# DisplayPort.net
KiCad netlist of a schematic drawn in Altium Designer
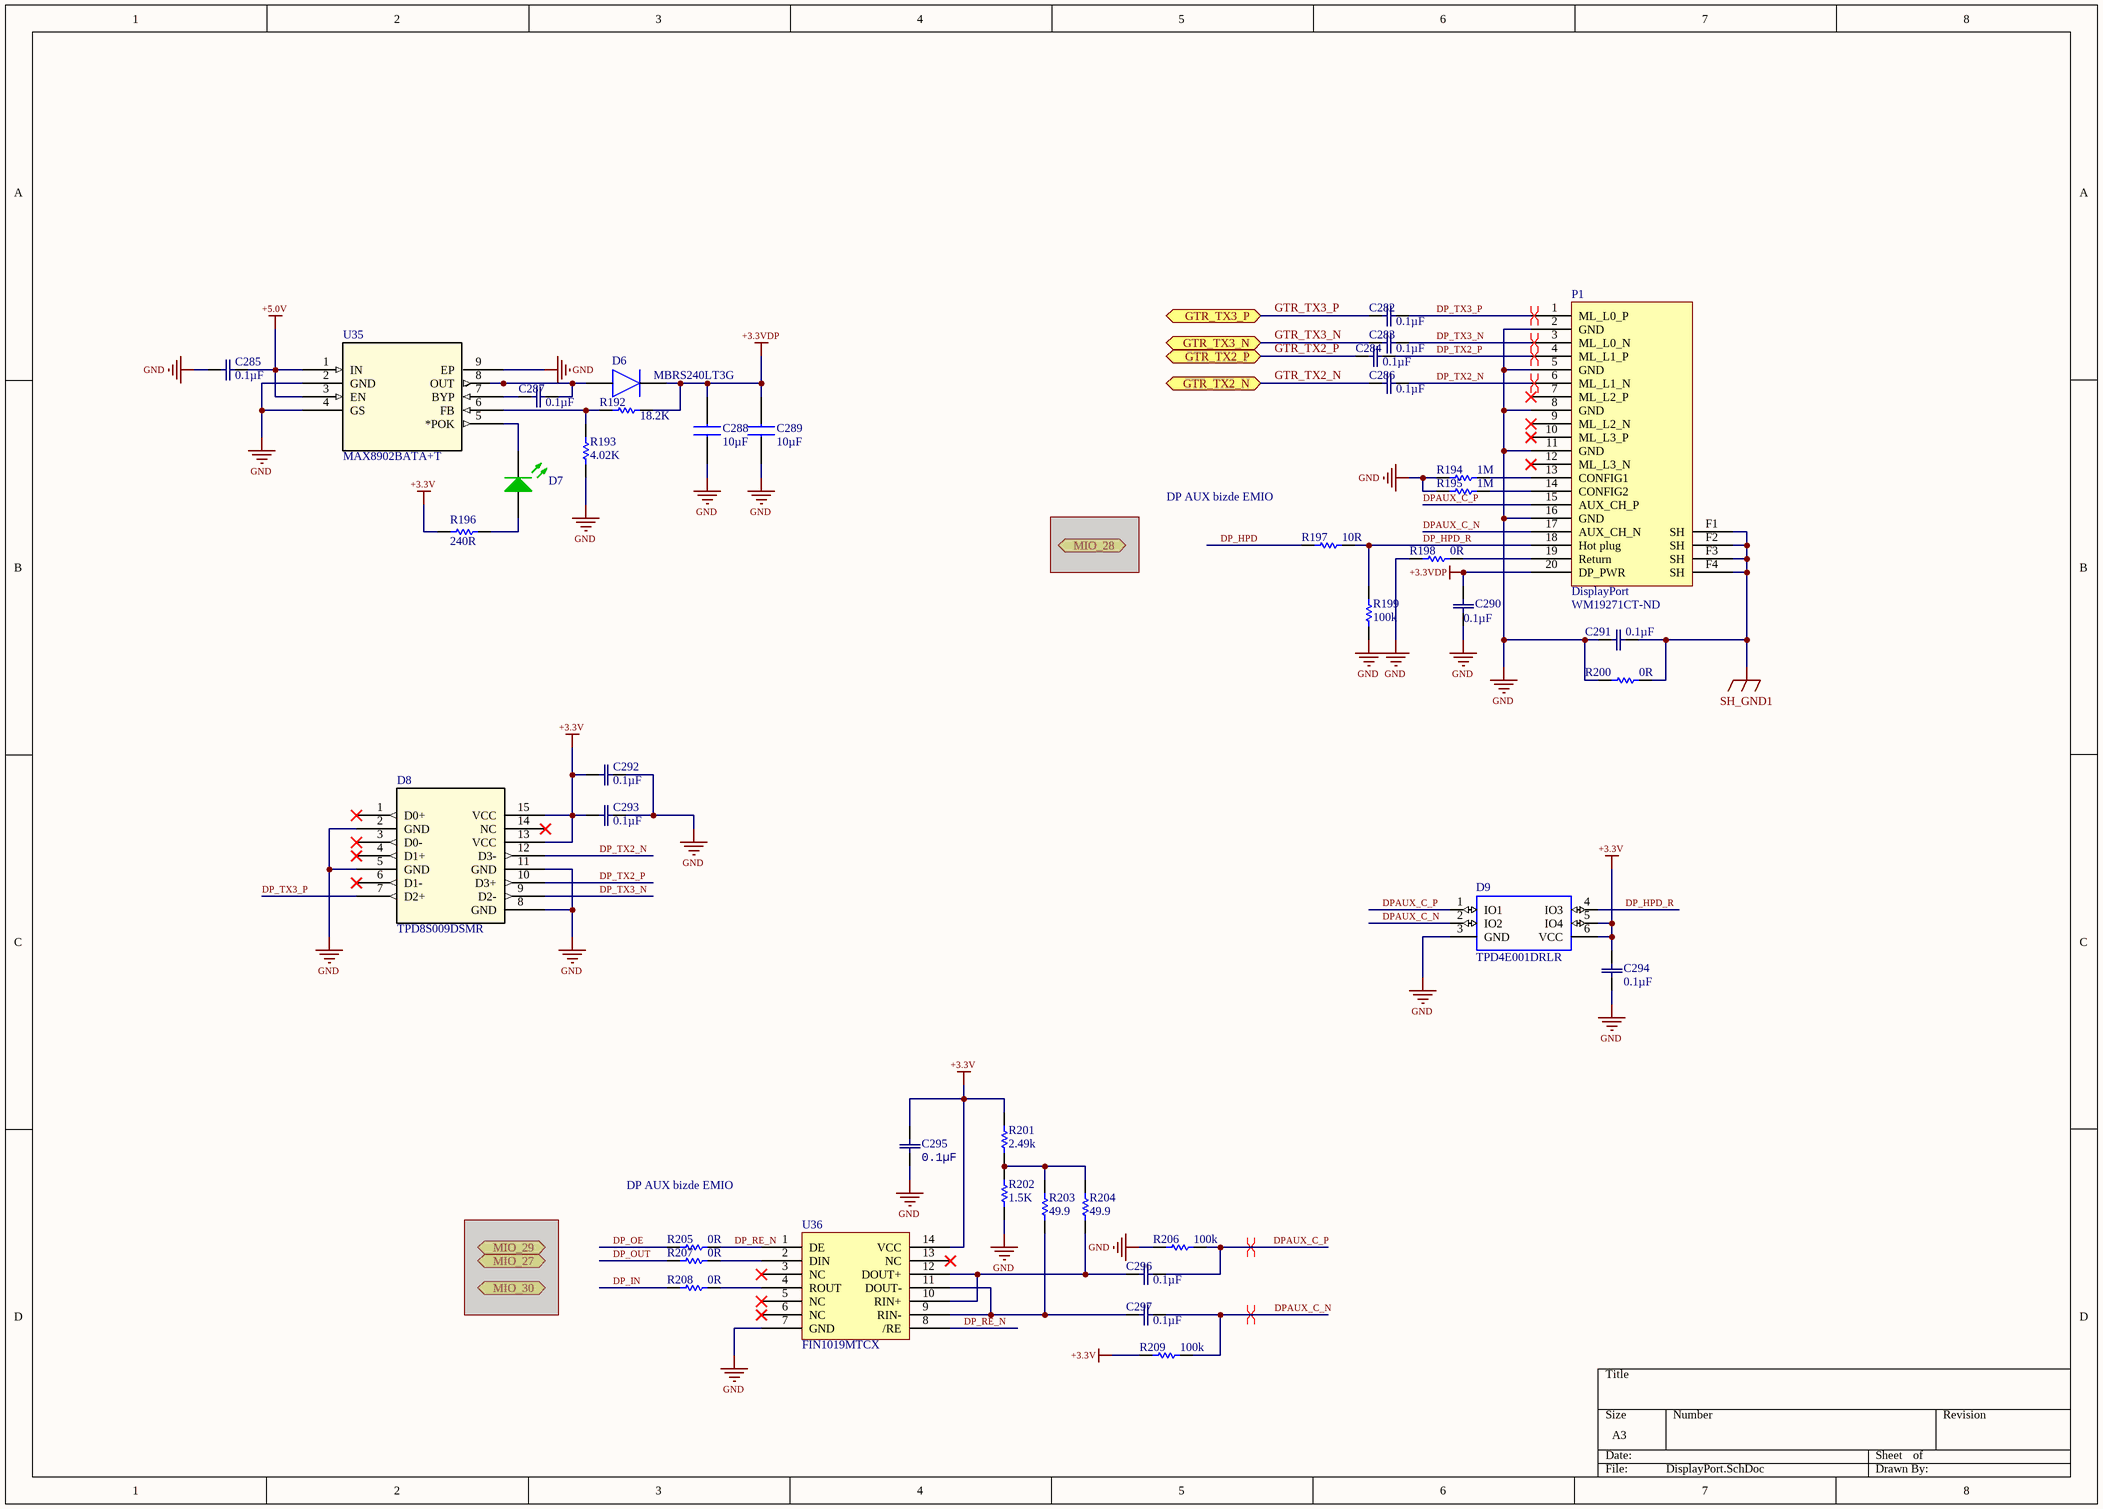
[diagram p0: DisplayPort.SchDoc]

(export (version "E")
  (design (tool "Eeschema 10.0.6"))
  (components
    (comp (ref "C282")
      (value "0.1µF")
      (footprint "CAP_0603")
      (description "CAP CER 0.1UF 25V 10% X5R 0201")
      (fields
        (field (name "MANUFACTURER_PART_NUMBER") "C0603X5R1E104K030BB")
        (field (name "DIGI-KEY PART NUMBER") "445-13671-1-ND")
      )
      (libsource (lib "Ultrascale_SchLib") (part "C0603X5R1E104K030BB"))
    )
    (comp (ref "C283")
      (value "0.1µF")
      (footprint "CAP_0603")
      (description "CAP CER 0.1UF 25V 10% X5R 0201")
      (fields
        (field (name "MANUFACTURER_PART_NUMBER") "C0603X5R1E104K030BB")
        (field (name "DIGI-KEY PART NUMBER") "445-13671-1-ND")
      )
      (libsource (lib "Ultrascale_SchLib") (part "C0603X5R1E104K030BB"))
    )
    (comp (ref "C284")
      (value "0.1µF")
      (footprint "CAP_0603")
      (description "CAP CER 0.1UF 25V 10% X5R 0201")
      (fields
        (field (name "MANUFACTURER_PART_NUMBER") "C0603X5R1E104K030BB")
        (field (name "DIGI-KEY PART NUMBER") "445-13671-1-ND")
      )
      (libsource (lib "Ultrascale_SchLib") (part "C0603X5R1E104K030BB"))
    )
    (comp (ref "C285")
      (value "0.1µF")
      (footprint "CAP_0603")
      (description "CAP CER 0.1UF 25V 10% X5R 0201")
      (fields
        (field (name "MANUFACTURER_PART_NUMBER") "C0603X5R1E104K030BB")
        (field (name "DIGI-KEY PART NUMBER") "445-13671-1-ND")
      )
      (libsource (lib "Ultrascale_SchLib") (part "C0603X5R1E104K030BB"))
    )
    (comp (ref "C286")
      (value "0.1µF")
      (footprint "CAP_0603")
      (description "CAP CER 0.1UF 25V 10% X5R 0201")
      (fields
        (field (name "MANUFACTURER_PART_NUMBER") "C0603X5R1E104K030BB")
        (field (name "DIGI-KEY PART NUMBER") "445-13671-1-ND")
      )
      (libsource (lib "Ultrascale_SchLib") (part "C0603X5R1E104K030BB"))
    )
    (comp (ref "C287")
      (value "0.1µF")
      (footprint "CAP_0603")
      (description "CAP CER 0.1UF 25V 10% X5R 0201")
      (fields
        (field (name "MANUFACTURER_PART_NUMBER") "C0603X5R1E104K030BB")
        (field (name "DIGI-KEY PART NUMBER") "445-13671-1-ND")
      )
      (libsource (lib "Ultrascale_SchLib") (part "C0603X5R1E104K030BB"))
    )
    (comp (ref "C288")
      (value "10µF")
      (footprint "CAP 0402ZD106")
      (description "CAP CER 10UF 10V X5R 0402")
      (fields
        (field (name "MANUFACTURER_PART_NUMBER") "0402ZD106MAT2A")
        (field (name "DIGI-KEY PART NUMBER") "478-10052-1-ND")
      )
      (libsource (lib "Ultrascale_SchLib") (part "CAP 0402ZD106"))
    )
    (comp (ref "C289")
      (value "10µF")
      (footprint "CAP 0402ZD106")
      (description "CAP CER 10UF 10V X5R 0402")
      (fields
        (field (name "MANUFACTURER_PART_NUMBER") "0402ZD106MAT2A")
        (field (name "DIGI-KEY PART NUMBER") "478-10052-1-ND")
      )
      (libsource (lib "Ultrascale_SchLib") (part "CAP 0402ZD106"))
    )
    (comp (ref "C290")
      (value "0.1µF")
      (footprint "CAP_0603")
      (description "CAP CER 0.1UF 25V 10% X5R 0201")
      (fields
        (field (name "MANUFACTURER_PART_NUMBER") "C0603X5R1E104K030BB")
        (field (name "DIGI-KEY PART NUMBER") "445-13671-1-ND")
      )
      (libsource (lib "Ultrascale_SchLib") (part "C0603X5R1E104K030BB"))
    )
    (comp (ref "C291")
      (value "0.1µF")
      (footprint "CAP_0603")
      (description "CAP CER 0.1UF 25V 10% X5R 0201")
      (fields
        (field (name "MANUFACTURER_PART_NUMBER") "C0603X5R1E104K030BB")
        (field (name "DIGI-KEY PART NUMBER") "445-13671-1-ND")
      )
      (libsource (lib "Ultrascale_SchLib") (part "C0603X5R1E104K030BB"))
    )
    (comp (ref "C292")
      (value "0.1µF")
      (footprint "CAP_0603")
      (description "CAP CER 0.1UF 25V 10% X5R 0201")
      (fields
        (field (name "MANUFACTURER_PART_NUMBER") "C0603X5R1E104K030BB")
        (field (name "DIGI-KEY PART NUMBER") "445-13671-1-ND")
      )
      (libsource (lib "Ultrascale_SchLib") (part "C0603X5R1E104K030BB"))
    )
    (comp (ref "C293")
      (value "0.1µF")
      (footprint "CAP_0603")
      (description "CAP CER 0.1UF 25V 10% X5R 0201")
      (fields
        (field (name "MANUFACTURER_PART_NUMBER") "C0603X5R1E104K030BB")
        (field (name "DIGI-KEY PART NUMBER") "445-13671-1-ND")
      )
      (libsource (lib "Ultrascale_SchLib") (part "C0603X5R1E104K030BB"))
    )
    (comp (ref "C294")
      (value "0.1µF")
      (footprint "CAP_0603")
      (description "CAP CER 0.1UF 25V 10% X5R 0201")
      (fields
        (field (name "MANUFACTURER_PART_NUMBER") "C0603X5R1E104K030BB")
        (field (name "DIGI-KEY PART NUMBER") "445-13671-1-ND")
      )
      (libsource (lib "Ultrascale_SchLib") (part "C0603X5R1E104K030BB"))
    )
    (comp (ref "C295")
      (value "0.1µF")
      (footprint "CAP_0603")
      (description "CAP CER 0.1UF 25V 10% X5R 0201")
      (fields
        (field (name "MANUFACTURER_PART_NUMBER") "C0603X5R1E104K030BB")
        (field (name "DIGI-KEY PART NUMBER") "445-13671-1-ND")
      )
      (libsource (lib "Ultrascale_SchLib") (part "C0603X5R1E104K030BB"))
    )
    (comp (ref "C296")
      (value "0.1µF")
      (footprint "CAP_0603")
      (description "CAP CER 0.1UF 25V 10% X5R 0201")
      (fields
        (field (name "MANUFACTURER_PART_NUMBER") "C0603X5R1E104K030BB")
        (field (name "DIGI-KEY PART NUMBER") "445-13671-1-ND")
      )
      (libsource (lib "Ultrascale_SchLib") (part "C0603X5R1E104K030BB"))
    )
    (comp (ref "C297")
      (value "0.1µF")
      (footprint "CAP_0603")
      (description "CAP CER 0.1UF 25V 10% X5R 0201")
      (fields
        (field (name "MANUFACTURER_PART_NUMBER") "C0603X5R1E104K030BB")
        (field (name "DIGI-KEY PART NUMBER") "445-13671-1-ND")
      )
      (libsource (lib "Ultrascale_SchLib") (part "C0603X5R1E104K030BB"))
    )
    (comp (ref "D6")
      (value "MBRS240LT3G")
      (footprint "DIOM5436X247N")
      (description "DIODE SCHOTTKY 40V 2A SMB")
      (fields (field (name "RS PART NUMBER") "1022262"))
      (libsource (lib "Ultrascale_SchLib") (part "D MBRS240LT3G"))
    )
    (comp (ref "D7")
      (value "LED0603GREEN")
      (footprint "LED0603GREEN")
      (description "LED GREEN DIFFUSED 0603 SMD")
      (libsource (lib "Ultrascale_SchLib") (part "LED0603GREEN"))
    )
    (comp (ref "D8")
      (value "TPD8S009DSMR")
      (footprint "DSM15")
      (description "TVS DIODE 5.5VWM 15SON")
      (fields
        (field (name "RS_PART_NUMBER") "7099082")
        (field (name "COPYRIGHT") "Copyright (C) 2015 Accelerated Designs. All rights reserved")
      )
      (libsource (lib "Ultrascale_SchLib") (part "TPD8S009DSMR"))
    )
    (comp (ref "D9")
      (value "TPD4E001DRLR")
      (footprint "SOTFL50P160X60-6N")
      (description "Low-Capacitance 4-Channel +/-15-kV ESD Protection Array for High-Speed Data Interfaces")
      (fields (field (name "DIGI-KEY PART NUMBER") "296-21887-1-ND"))
      (libsource (lib "Ultrascale_SchLib") (part "D TPD4E001DRLR"))
    )
    (comp (ref "P1")
      (value "DisplayPort")
      (footprint "8470-2-2-X")
      (description "CONN RCPT 20POS UDI R/A SMD")
      (fields
        (field (name "MANUFACTURER") "Molex, LLC")
        (field (name "DIGI-KEY PART NUMBER") "WM19271CT-ND")
        (field (name "SUPPLIER PART NUMBER 1") "WM19271CT-ND")
      )
      (libsource (lib "Ultrascale_SchLib") (part "DisplayPort"))
    )
    (comp (ref "R192")
      (value "18.2K")
      (footprint "RES_CRCW_0402")
      (description "RES SMD 18.2K OHM 1% 1/16W 0402")
      (fields
        (field (name "MANUFACTURER_PART_NUMBER") "CRCW040218K2FKED")
        (field (name "RS_PART_NUMBER") "6784684")
        (field (name "COPYRIGHT") "Copyright (C) 2015 Accelerated Designs. All rights reserved")
      )
      (libsource (lib "Ultrascale_SchLib") (part "RES0402_18K2"))
    )
    (comp (ref "R193")
      (value "4.02K")
      (footprint "RC0402N")
      (description "RES SMD 4.02K OHM 1% 1/16W 0402")
      (fields
        (field (name "DIGIKEYPARTNUMBER") "541-0.0JTR-ND")
        (field (name "MANUFACTURER_PART_NUMBER") "CRCW04024K02FKED")
        (field (name "COPYRIGHT") "Copyright (C) 2015 Accelerated Designs. All rights reserved")
      )
      (libsource (lib "Ultrascale_SchLib") (part "RES0402_4K02"))
    )
    (comp (ref "R194")
      (value "1M")
      (footprint "RESC1005L_0402")
      (description "RES SMD 1M OHM 1% 1/16W 0402")
      (fields (field (name "POWER") "0.063W, 1/16W") (field (name "TOLERANCE") "1%"))
      (libsource (lib "Ultrascale_SchLib") (part "RES0402_1M"))
    )
    (comp (ref "R195")
      (value "1M")
      (footprint "RESC1005L_0402")
      (description "RES SMD 1M OHM 1% 1/16W 0402")
      (fields (field (name "POWER") "0.063W, 1/16W") (field (name "TOLERANCE") "1%"))
      (libsource (lib "Ultrascale_SchLib") (part "RES0402_1M"))
    )
    (comp (ref "R196")
      (value "240R")
      (footprint "RESC1005L_0402")
      (description "RES SMD 240 OHM 1% 1/10W 0402")
      (fields (field (name "POWER") "1/10W") (field (name "TOLERANCE") "1%"))
      (libsource (lib "Ultrascale_SchLib") (part "RES0402_240R_0W1_1T"))
    )
    (comp (ref "R197")
      (value "10R")
      (footprint "RESC1005L_0402")
      (description "RES SMD 10 OHM 1% 1/16W 0402")
      (fields (field (name "POWER") "0.063W, 1/16W") (field (name "Comment") "RES0402_10R"))
      (libsource (lib "Ultrascale_SchLib") (part "RES0402_10R"))
    )
    (comp (ref "R198")
      (value "0R")
      (footprint "RESC1005L_0402")
      (description "RES SMD 0 OHM JUMPER 1/16W 0402")
      (fields (field (name "POWER") "0.063W, 1/16W") (field (name "Comment") "RES0402_0R"))
      (libsource (lib "Ultrascale_SchLib") (part "RES0402_0R"))
    )
    (comp (ref "R199")
      (value "100k")
      (footprint "RESC1005L_0402")
      (description "RES SMD 100K OHM 1% 1/5W 0402")
      (fields (field (name "POWER") "1/5W") (field (name "TOLERANCE") "1%"))
      (libsource (lib "Ultrascale_SchLib") (part "RES0402_100K_0W2_1T"))
    )
    (comp (ref "R200")
      (value "0R")
      (footprint "RESC1005L_0402")
      (description "RES SMD 0 OHM JUMPER 1/10W 0402")
      (fields (field (name "POWER") "1/10W") (field (name "Comment") "RES0402_0R_0W1"))
      (libsource (lib "Ultrascale_SchLib") (part "RES0402_0R_0W1"))
    )
    (comp (ref "R201")
      (value "2.49k")
      (footprint "RESC1005L_0402")
      (description "RES SMD 2.49K OHM 1% 1/10W 0402")
      (fields (field (name "POWER") "1/10W") (field (name "TOLERANCE") "1%"))
      (libsource (lib "Ultrascale_SchLib") (part "RES0402_2K49_0W1_1T"))
    )
    (comp (ref "R202")
      (value "1.5K")
      (footprint "RESC1005L_0402")
      (description "RES SMD 1.5K OHM 1% 1/16W 0402")
      (fields (field (name "POWER") "1/10W") (field (name "TOLERANCE") "1%"))
      (libsource (lib "Ultrascale_SchLib") (part "RES0402_1K5"))
    )
    (comp (ref "R203")
      (value "49.9")
      (footprint "RESC1005L_0402")
      (description "RES SMD 49.9 OHM 1% 1/16W 0402")
      (fields (field (name "POWER") "0.063W, 1/16W") (field (name "TOLERANCE") "1%"))
      (libsource (lib "Ultrascale_SchLib") (part "RES0402_49.9"))
    )
    (comp (ref "R204")
      (value "49.9")
      (footprint "RESC1005L_0402")
      (description "RES SMD 49.9 OHM 1% 1/16W 0402")
      (fields (field (name "POWER") "0.063W, 1/16W") (field (name "TOLERANCE") "1%"))
      (libsource (lib "Ultrascale_SchLib") (part "RES0402_49.9"))
    )
    (comp (ref "R205")
      (value "0R")
      (footprint "RESC1005L_0402")
      (description "RES SMD 0 OHM JUMPER 1/16W 0402")
      (fields (field (name "POWER") "0.063W, 1/16W") (field (name "Comment") "RES0402_0R"))
      (libsource (lib "Ultrascale_SchLib") (part "RES0402_0R"))
    )
    (comp (ref "R206")
      (value "100k")
      (footprint "RESC1005L_0402")
      (description "RES SMD 100K OHM 1% 1/5W 0402")
      (fields (field (name "POWER") "1/5W") (field (name "TOLERANCE") "1%"))
      (libsource (lib "Ultrascale_SchLib") (part "RES0402_100K_0W2_1T"))
    )
    (comp (ref "R207")
      (value "0R")
      (footprint "RESC1005L_0402")
      (description "RES SMD 0 OHM JUMPER 1/16W 0402")
      (fields (field (name "POWER") "0.063W, 1/16W") (field (name "Comment") "RES0402_0R"))
      (libsource (lib "Ultrascale_SchLib") (part "RES0402_0R"))
    )
    (comp (ref "R208")
      (value "0R")
      (footprint "RESC1005L_0402")
      (description "RES SMD 0 OHM JUMPER 1/16W 0402")
      (fields (field (name "POWER") "0.063W, 1/16W") (field (name "Comment") "RES0402_0R"))
      (libsource (lib "Ultrascale_SchLib") (part "RES0402_0R"))
    )
    (comp (ref "R209")
      (value "100k")
      (footprint "RESC1005L_0402")
      (description "RES SMD 100K OHM 1% 1/5W 0402")
      (fields (field (name "POWER") "1/5W") (field (name "TOLERANCE") "1%"))
      (libsource (lib "Ultrascale_SchLib") (part "RES0402_100K_0W2_1T"))
    )
    (comp (ref "U35")
      (value "MAX8902BATA+T")
      (footprint "21-0168E_T822-1")
      (description "IC REG LDO ADJ 0.5A 8TDFN")
      (fields (field (name "COPYRIGHT") "Copyright (C) 2015 Accelerated Designs. All rights reserved"))
      (libsource (lib "Ultrascale_SchLib") (part "MAX8902BATA+T"))
    )
    (comp (ref "U36")
      (value "FIN1019MTCX")
      (footprint "TSOP65P640X120-14N")
      (description "IC DRVR/RCVR3.3V LVDS HS 14TSSOP")
      (fields
        (field (name "DIGI-KEY PART NUMBER") "FIN1019MTCXCT-ND")
        (field (name "MANUFACTURER") "Fairchild/ON Semiconductor")
      )
      (libsource (lib "Ultrascale_SchLib") (part "FIN1019MTCX"))
    )
  )
  (nets
    (net (code "1") (name "+3.3V") (class "Default")
      (node (ref "C292") (pin "2") (pinfunction "2_2") (pintype "passive"))
      (node (ref "C293") (pin "2") (pinfunction "2_2") (pintype "passive"))
      (node (ref "C294") (pin "2") (pinfunction "2_2") (pintype "passive"))
      (node (ref "C295") (pin "2") (pinfunction "2_2") (pintype "passive"))
      (node (ref "D8") (pin "13") (pinfunction "VCC_13") (pintype "power_in"))
      (node (ref "D8") (pin "15") (pinfunction "VCC_15") (pintype "power_in"))
      (node (ref "D9") (pin "5") (pinfunction "IO4_5") (pintype "bidirectional"))
      (node (ref "D9") (pin "6") (pinfunction "VCC_6") (pintype "power_in"))
      (node (ref "R196") (pin "1") (pinfunction "1_1") (pintype "passive"))
      (node (ref "R201") (pin "2") (pinfunction "2_2") (pintype "passive"))
      (node (ref "R209") (pin "1") (pinfunction "1_1") (pintype "passive"))
      (node (ref "U36") (pin "14") (pinfunction "VCC_14") (pintype "power_in"))
    )
    (net (code "2") (name "+3.3VDP") (class "Default")
      (node (ref "C288") (pin "2") (pinfunction "2_2") (pintype "passive"))
      (node (ref "C289") (pin "2") (pinfunction "2_2") (pintype "passive"))
      (node (ref "C290") (pin "2") (pinfunction "2_2") (pintype "passive"))
      (node (ref "D6") (pin "1") (pinfunction "K_1") (pintype "passive"))
      (node (ref "P1") (pin "20") (pinfunction "DP_PWR_20") (pintype "power_in"))
      (node (ref "R192") (pin "2") (pinfunction "2_2") (pintype "passive"))
    )
    (net (code "3") (name "+5.0V") (class "Default")
      (node (ref "C285") (pin "2") (pinfunction "2_2") (pintype "passive"))
      (node (ref "U35") (pin "1") (pinfunction "IN_1") (pintype "input"))
      (node (ref "U35") (pin "3") (pinfunction "EN_3") (pintype "input"))
    )
    (net (code "4") (name "/DPAUX_C_N") (class "Default")
      (node (ref "C297") (pin "2") (pinfunction "2_2") (pintype "passive"))
      (node (ref "D9") (pin "2") (pinfunction "IO2_2") (pintype "bidirectional"))
      (node (ref "P1") (pin "17") (pinfunction "AUX_CH_N_17") (pintype "power_in"))
      (node (ref "R209") (pin "2") (pinfunction "2_2") (pintype "passive"))
    )
    (net (code "5") (name "/DPAUX_C_P") (class "Default")
      (node (ref "C296") (pin "2") (pinfunction "2_2") (pintype "passive"))
      (node (ref "D9") (pin "1") (pinfunction "IO1_1") (pintype "bidirectional"))
      (node (ref "P1") (pin "15") (pinfunction "AUX_CH_P_15") (pintype "power_in"))
      (node (ref "R206") (pin "2") (pinfunction "2_2") (pintype "passive"))
    )
    (net (code "6") (name "/DP_HPD") (class "Default")
      (node (ref "R197") (pin "1") (pinfunction "1_1") (pintype "passive"))
    )
    (net (code "7") (name "/DP_HPD_R") (class "Default")
      (node (ref "D9") (pin "4") (pinfunction "IO3_4") (pintype "bidirectional"))
      (node (ref "P1") (pin "18") (pinfunction "Hot_plug_18") (pintype "power_in"))
      (node (ref "R197") (pin "2") (pinfunction "2_2") (pintype "passive"))
      (node (ref "R199") (pin "2") (pinfunction "2_2") (pintype "passive"))
    )
    (net (code "8") (name "/DP_IN") (class "Default")
      (node (ref "R208") (pin "1") (pinfunction "1_1") (pintype "passive"))
    )
    (net (code "9") (name "/DP_OE") (class "Default")
      (node (ref "R205") (pin "1") (pinfunction "1_1") (pintype "passive"))
    )
    (net (code "10") (name "/DP_OUT") (class "Default")
      (node (ref "R207") (pin "1") (pinfunction "1_1") (pintype "passive"))
    )
    (net (code "11") (name "/DP_RE_N") (class "Default")
      (node (ref "R205") (pin "2") (pinfunction "2_2") (pintype "passive"))
      (node (ref "U36") (pin "1") (pinfunction "DE_1") (pintype "power_in"))
      (node (ref "U36") (pin "8") (pinfunction "/RE_8") (pintype "power_in"))
    )
    (net (code "12") (name "/DP_TX2_N") (class "Default")
      (node (ref "C286") (pin "2") (pinfunction "2_2") (pintype "passive"))
      (node (ref "D8") (pin "12") (pinfunction "D3-_12") (pintype "output"))
      (node (ref "P1") (pin "6") (pinfunction "ML_L1_N_6") (pintype "power_in"))
    )
    (net (code "13") (name "/DP_TX2_P") (class "Default")
      (node (ref "C284") (pin "2") (pinfunction "2_2") (pintype "passive"))
      (node (ref "D8") (pin "10") (pinfunction "D3+_10") (pintype "output"))
      (node (ref "P1") (pin "4") (pinfunction "ML_L1_P_4") (pintype "power_in"))
    )
    (net (code "14") (name "/DP_TX3_N") (class "Default")
      (node (ref "C283") (pin "2") (pinfunction "2_2") (pintype "passive"))
      (node (ref "D8") (pin "9") (pinfunction "D2-_9") (pintype "output"))
      (node (ref "P1") (pin "3") (pinfunction "ML_L0_N_3") (pintype "power_in"))
    )
    (net (code "15") (name "/DP_TX3_P") (class "Default")
      (node (ref "C282") (pin "2") (pinfunction "2_2") (pintype "passive"))
      (node (ref "D8") (pin "7") (pinfunction "D2+_7") (pintype "output"))
      (node (ref "P1") (pin "1") (pinfunction "ML_L0_P_1") (pintype "power_in"))
    )
    (net (code "16") (name "/GTR_TX2_N") (class "Default")
      (node (ref "C286") (pin "1") (pinfunction "1_1") (pintype "passive"))
    )
    (net (code "17") (name "/GTR_TX2_P") (class "Default")
      (node (ref "C284") (pin "1") (pinfunction "1_1") (pintype "passive"))
    )
    (net (code "18") (name "/GTR_TX3_N") (class "Default")
      (node (ref "C283") (pin "1") (pinfunction "1_1") (pintype "passive"))
    )
    (net (code "19") (name "/GTR_TX3_P") (class "Default")
      (node (ref "C282") (pin "1") (pinfunction "1_1") (pintype "passive"))
    )
    (net (code "24") (name "GND") (class "Default")
      (node (ref "C285") (pin "1") (pinfunction "1_1") (pintype "passive"))
      (node (ref "C288") (pin "1") (pinfunction "1_1") (pintype "passive"))
      (node (ref "C289") (pin "1") (pinfunction "1_1") (pintype "passive"))
      (node (ref "C290") (pin "1") (pinfunction "1_1") (pintype "passive"))
      (node (ref "C291") (pin "1") (pinfunction "1_1") (pintype "passive"))
      (node (ref "C292") (pin "1") (pinfunction "1_1") (pintype "passive"))
      (node (ref "C293") (pin "1") (pinfunction "1_1") (pintype "passive"))
      (node (ref "C294") (pin "1") (pinfunction "1_1") (pintype "passive"))
      (node (ref "C295") (pin "1") (pinfunction "1_1") (pintype "passive"))
      (node (ref "D8") (pin "11") (pinfunction "GND_11") (pintype "power_in"))
      (node (ref "D8") (pin "2") (pinfunction "GND_2") (pintype "power_in"))
      (node (ref "D8") (pin "5") (pinfunction "GND_5") (pintype "power_in"))
      (node (ref "D8") (pin "8") (pinfunction "GND_8") (pintype "power_in"))
      (node (ref "D9") (pin "3") (pinfunction "GND_3") (pintype "passive"))
      (node (ref "P1") (pin "11") (pinfunction "GND_11") (pintype "power_in"))
      (node (ref "P1") (pin "16") (pinfunction "GND_16") (pintype "power_in"))
      (node (ref "P1") (pin "2") (pinfunction "GND_2") (pintype "power_in"))
      (node (ref "P1") (pin "5") (pinfunction "GND_5") (pintype "power_in"))
      (node (ref "P1") (pin "8") (pinfunction "GND_8") (pintype "power_in"))
      (node (ref "R193") (pin "1") (pinfunction "1_1") (pintype "passive"))
      (node (ref "R194") (pin "1") (pinfunction "1_1") (pintype "passive"))
      (node (ref "R195") (pin "1") (pinfunction "1_1") (pintype "passive"))
      (node (ref "R198") (pin "1") (pinfunction "1_1") (pintype "passive"))
      (node (ref "R199") (pin "1") (pinfunction "1_1") (pintype "passive"))
      (node (ref "R200") (pin "1") (pinfunction "1_1") (pintype "passive"))
      (node (ref "R202") (pin "1") (pinfunction "1_1") (pintype "passive"))
      (node (ref "R206") (pin "1") (pinfunction "1_1") (pintype "passive"))
      (node (ref "U35") (pin "2") (pinfunction "GND_2") (pintype "power_in"))
      (node (ref "U35") (pin "4") (pinfunction "GS_4") (pintype "passive"))
      (node (ref "U35") (pin "9") (pinfunction "EP_9") (pintype "passive"))
      (node (ref "U36") (pin "7") (pinfunction "GND_7") (pintype "power_in"))
    )
    (net (code "25") (name "Net-(D6-A)") (class "Default")
      (node (ref "C287") (pin "2") (pinfunction "2_2") (pintype "passive"))
      (node (ref "D6") (pin "2") (pinfunction "A_2") (pintype "passive"))
      (node (ref "U35") (pin "8") (pinfunction "OUT_8") (pintype "output"))
    )
    (net (code "26") (name "Net-(D7-A)") (class "Default")
      (node (ref "D7") (pin "1") (pinfunction "A_1") (pintype "passive"))
      (node (ref "R196") (pin "2") (pinfunction "2_2") (pintype "passive"))
    )
    (net (code "27") (name "Net-(D7-K)") (class "Default")
      (node (ref "D7") (pin "2") (pinfunction "K_2") (pintype "passive"))
      (node (ref "U35") (pin "5") (pinfunction "*POK_5") (pintype "output"))
    )
    (net (code "28") (name "Net-(P1-CONFIG1)") (class "Default")
      (node (ref "P1") (pin "13") (pinfunction "CONFIG1_13") (pintype "power_in"))
      (node (ref "R194") (pin "2") (pinfunction "2_2") (pintype "passive"))
    )
    (net (code "29") (name "Net-(P1-CONFIG2)") (class "Default")
      (node (ref "P1") (pin "14") (pinfunction "CONFIG2_14") (pintype "power_in"))
      (node (ref "R195") (pin "2") (pinfunction "2_2") (pintype "passive"))
    )
    (net (code "30") (name "Net-(P1-Return)") (class "Default")
      (node (ref "P1") (pin "19") (pinfunction "Return_19") (pintype "power_in"))
      (node (ref "R198") (pin "2") (pinfunction "2_2") (pintype "passive"))
    )
    (net (code "31") (name "Net-(R201-Pad1)") (class "Default")
      (node (ref "R201") (pin "1") (pinfunction "1_1") (pintype "passive"))
      (node (ref "R202") (pin "2") (pinfunction "2_2") (pintype "passive"))
      (node (ref "R203") (pin "2") (pinfunction "2_2") (pintype "passive"))
      (node (ref "R204") (pin "2") (pinfunction "2_2") (pintype "passive"))
    )
    (net (code "32") (name "Net-(U35-BYP)") (class "Default")
      (node (ref "C287") (pin "1") (pinfunction "1_1") (pintype "passive"))
      (node (ref "U35") (pin "7") (pinfunction "BYP_7") (pintype "input"))
    )
    (net (code "33") (name "Net-(U35-FB)") (class "Default")
      (node (ref "R192") (pin "1") (pinfunction "1_1") (pintype "passive"))
      (node (ref "R193") (pin "2") (pinfunction "2_2") (pintype "passive"))
      (node (ref "U35") (pin "6") (pinfunction "FB_6") (pintype "input"))
    )
    (net (code "34") (name "Net-(U36-DIN)") (class "Default")
      (node (ref "R207") (pin "2") (pinfunction "2_2") (pintype "passive"))
      (node (ref "U36") (pin "2") (pinfunction "DIN_2") (pintype "power_in"))
    )
    (net (code "35") (name "Net-(U36-DOUT+)") (class "Default")
      (node (ref "C296") (pin "1") (pinfunction "1_1") (pintype "passive"))
      (node (ref "R204") (pin "1") (pinfunction "1_1") (pintype "passive"))
      (node (ref "U36") (pin "10") (pinfunction "RIN+_10") (pintype "power_in"))
      (node (ref "U36") (pin "12") (pinfunction "DOUT+_12") (pintype "power_in"))
    )
    (net (code "36") (name "Net-(U36-DOUT-)") (class "Default")
      (node (ref "C297") (pin "1") (pinfunction "1_1") (pintype "passive"))
      (node (ref "R203") (pin "1") (pinfunction "1_1") (pintype "passive"))
      (node (ref "U36") (pin "11") (pinfunction "DOUT-_11") (pintype "power_in"))
      (node (ref "U36") (pin "9") (pinfunction "RIN-_9") (pintype "power_in"))
    )
    (net (code "37") (name "Net-(U36-ROUT)") (class "Default")
      (node (ref "R208") (pin "2") (pinfunction "2_2") (pintype "passive"))
      (node (ref "U36") (pin "4") (pinfunction "ROUT_4") (pintype "power_in"))
    )
    (net (code "38") (name "SH_GND1") (class "Default")
      (node (ref "C291") (pin "2") (pinfunction "2_2") (pintype "passive"))
      (node (ref "P1") (pin "F1") (pinfunction "SH_F1") (pintype "power_in"))
      (node (ref "P1") (pin "F2") (pinfunction "SH_F2") (pintype "power_in"))
      (node (ref "P1") (pin "F3") (pinfunction "SH_F3") (pintype "power_in"))
      (node (ref "P1") (pin "F4") (pinfunction "SH_F4") (pintype "power_in"))
      (node (ref "R200") (pin "2") (pinfunction "2_2") (pintype "passive"))
    )
    (net (code "39") (name "unconnected-(D8-D0+-Pad1)") (class "Default")
      (node (ref "D8") (pin "1") (pinfunction "D0+_1") (pintype "output+no_connect"))
    )
    (net (code "40") (name "unconnected-(D8-D0--Pad3)") (class "Default")
      (node (ref "D8") (pin "3") (pinfunction "D0-_3") (pintype "output+no_connect"))
    )
    (net (code "41") (name "unconnected-(D8-D1+-Pad4)") (class "Default")
      (node (ref "D8") (pin "4") (pinfunction "D1+_4") (pintype "output+no_connect"))
    )
    (net (code "42") (name "unconnected-(D8-D1--Pad6)") (class "Default")
      (node (ref "D8") (pin "6") (pinfunction "D1-_6") (pintype "output+no_connect"))
    )
    (net (code "43") (name "unconnected-(D8-NC-Pad14)") (class "Default")
      (node (ref "D8") (pin "14") (pinfunction "NC_14") (pintype "passive+no_connect"))
    )
    (net (code "44") (name "unconnected-(P1-ML_L2_N-Pad9)") (class "Default")
      (node (ref "P1") (pin "9") (pinfunction "ML_L2_N_9") (pintype "power_in+no_connect"))
    )
    (net (code "45") (name "unconnected-(P1-ML_L2_P-Pad7)") (class "Default")
      (node (ref "P1") (pin "7") (pinfunction "ML_L2_P_7") (pintype "power_in+no_connect"))
    )
    (net (code "46") (name "unconnected-(P1-ML_L3_N-Pad12)") (class "Default")
      (node (ref "P1") (pin "12") (pinfunction "ML_L3_N_12") (pintype "power_in+no_connect"))
    )
    (net (code "47") (name "unconnected-(P1-ML_L3_P-Pad10)") (class "Default")
      (node (ref "P1") (pin "10") (pinfunction "ML_L3_P_10") (pintype "power_in+no_connect"))
    )
    (net (code "48") (name "unconnected-(U36-NC-Pad3)") (class "Default")
      (node (ref "U36") (pin "3") (pinfunction "NC_3") (pintype "power_in+no_connect"))
    )
    (net (code "49") (name "unconnected-(U36-NC-Pad5)") (class "Default")
      (node (ref "U36") (pin "5") (pinfunction "NC_5") (pintype "power_in+no_connect"))
    )
    (net (code "50") (name "unconnected-(U36-NC-Pad6)") (class "Default")
      (node (ref "U36") (pin "6") (pinfunction "NC_6") (pintype "power_in+no_connect"))
    )
    (net (code "51") (name "unconnected-(U36-NC-Pad13)") (class "Default")
      (node (ref "U36") (pin "13") (pinfunction "NC_13") (pintype "power_in+no_connect"))
    )
  )
)
